# 3_waffling80-NMB_mcu.net
KiCad netlist of a schematic drawn in Altium Designer
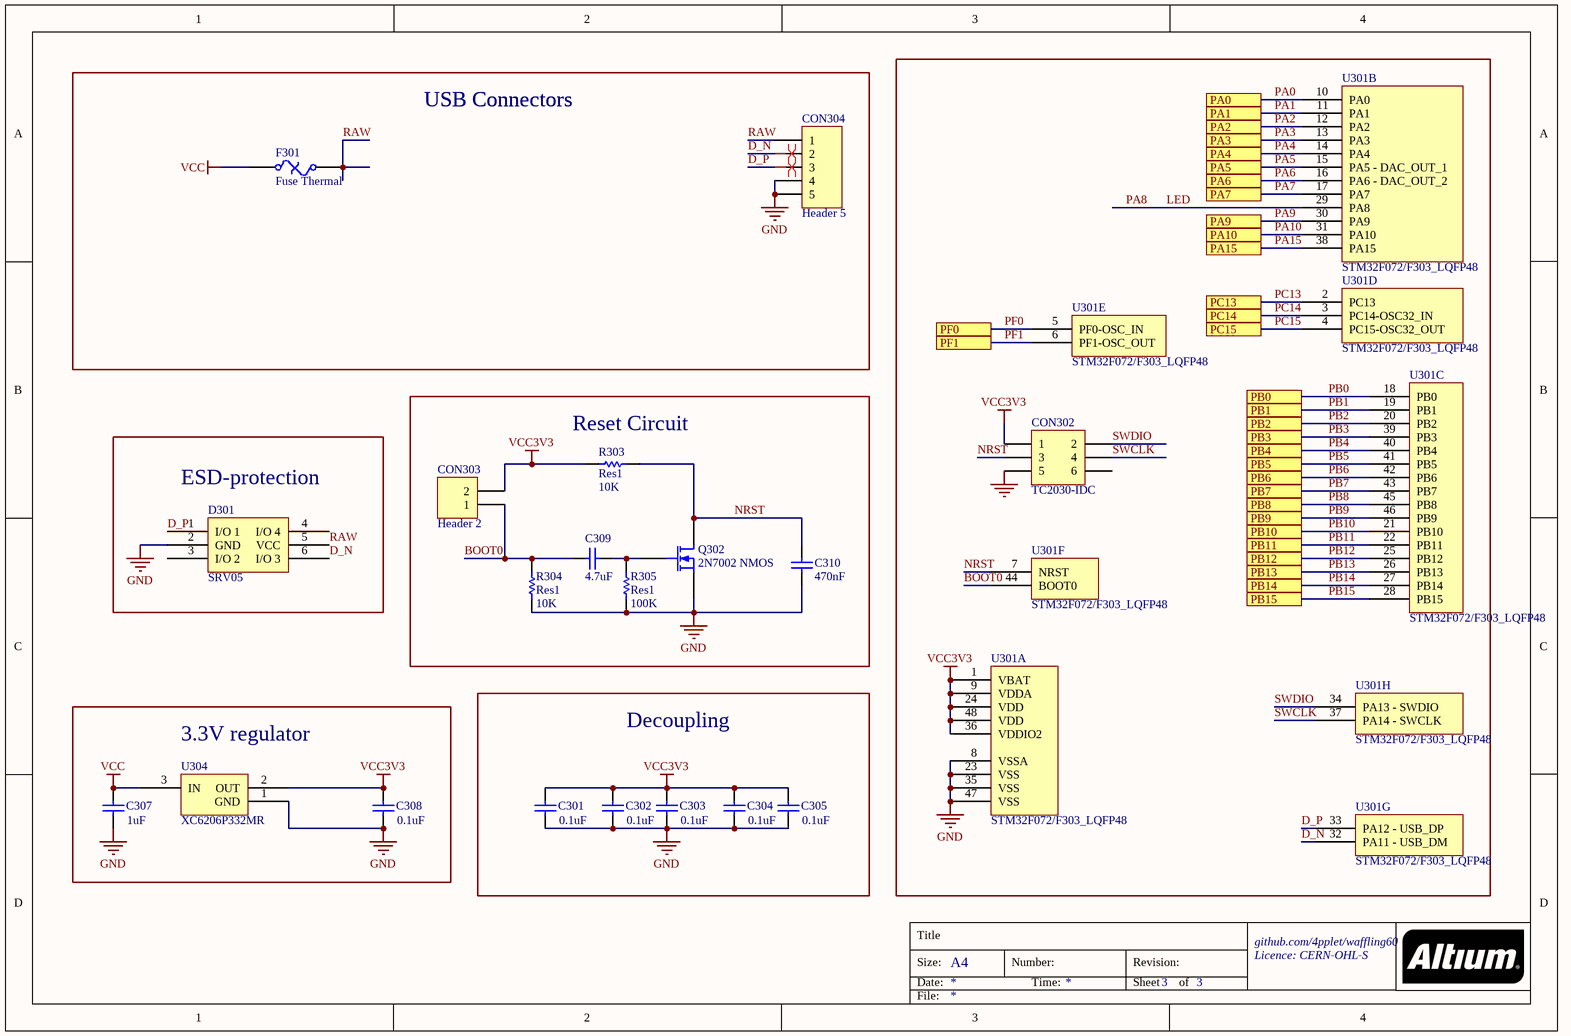
[diagram p0: 3_waffling80-NMB_mcu.SchDoc]

(export (version "E")
  (design (tool "Eeschema 10.0.6"))
  (components
    (comp (ref "C301")
      (value "0.1uF")
      (footprint "C0603[1608]")
      (description "Capacitor")
      (fields (field (name "LCSC PART #") "C14663") (field (name "MRF.PART") "CC0603KRX7R9BB104"))
      (libsource (lib "Miscellaneous Devices") (part "Cap"))
    )
    (comp (ref "C302")
      (value "0.1uF")
      (footprint "C0603[1608]")
      (description "Capacitor")
      (fields (field (name "LCSC PART #") "C14663") (field (name "MRF.PART") "CC0603KRX7R9BB104"))
      (libsource (lib "Miscellaneous Devices") (part "Cap"))
    )
    (comp (ref "C303")
      (value "0.1uF")
      (footprint "C0603[1608]")
      (description "Capacitor")
      (fields (field (name "LCSC PART #") "C14663") (field (name "MRF.PART") "CC0603KRX7R9BB104"))
      (libsource (lib "Miscellaneous Devices") (part "Cap"))
    )
    (comp (ref "C304")
      (value "0.1uF")
      (footprint "C0603[1608]")
      (description "Capacitor")
      (fields (field (name "LCSC PART #") "C14663") (field (name "MRF.PART") "CC0603KRX7R9BB104"))
      (libsource (lib "Miscellaneous Devices") (part "Cap"))
    )
    (comp (ref "C305")
      (value "0.1uF")
      (footprint "C0603[1608]")
      (description "Capacitor")
      (fields (field (name "LCSC PART #") "C14663") (field (name "MRF.PART") "CC0603KRX7R9BB104"))
      (libsource (lib "Miscellaneous Devices") (part "Cap"))
    )
    (comp (ref "C307")
      (value "1uF")
      (footprint "C0603[1608]")
      (description "Capacitor")
      (fields (field (name "LCSC PART #") "C15849") (field (name "MRF.PART") "CL10A105KB8NNNC"))
      (libsource (lib "Miscellaneous Devices") (part "Cap"))
    )
    (comp (ref "C308")
      (value "0.1uF")
      (footprint "C0603[1608]")
      (description "Capacitor")
      (fields (field (name "LCSC PART #") "C14663") (field (name "MRF.PART") "CC0603KRX7R9BB104"))
      (libsource (lib "Miscellaneous Devices") (part "Cap"))
    )
    (comp (ref "C309")
      (value "4.7uF")
      (footprint "C0603[1608]")
      (description "Capacitor")
      (fields (field (name "LCSC PART #") "C19666") (field (name "MRF.PART") "CL10A475KO8NNNC"))
      (libsource (lib "Miscellaneous Devices") (part "Cap"))
    )
    (comp (ref "C310")
      (value "470nF")
      (footprint "C0603[1608]")
      (description "Capacitor")
      (fields (field (name "LCSC PART #") "C1623") (field (name "MRF.PART") "CL10B474KA8NNNC"))
      (libsource (lib "Miscellaneous Devices") (part "Cap"))
    )
    (comp (ref "CON302")
      (value "TC2030-IDC")
      (footprint "TC2030-IDC-NL")
      (description "Header, 3-Pin, Dual row")
      (libsource (lib "Miscellaneous Connectors") (part "Header 3X2"))
    )
    (comp (ref "CON303")
      (value "Header 2")
      (footprint "HDR1X2")
      (description "Header, 2-Pin")
      (libsource (lib "Miscellaneous Connectors") (part "Header 2"))
    )
    (comp (ref "CON304")
      (value "Header 5")
      (footprint "UDB_COMBO_JST_MOLEX")
      (description "JST for USB daughter board")
      (fields (field (name "LCSC PART #") "C160404") (field (name "MRF.PART") "SM04B-SRSS-TB(LF)(SN)"))
      (libsource (lib "Miscellaneous Connectors") (part "Header 5"))
    )
    (comp (ref "D301")
      (value "SRV05")
      (footprint "SOT-23-6")
      (fields (field (name "LCSC PART #") "C85364") (field (name "MRF.PART") "SRV05-4-P-T7"))
      (libsource (lib "Keebs") (part "SRV05"))
    )
    (comp (ref "F301")
      (value "Fuse Thermal")
      (footprint "C1206[3216]")
      (description "Thermal Fuse")
      (fields (field (name "LCSC PART #") "C135338") (field (name "MRF.PART") "ASMD1206-050"))
      (libsource (lib "Miscellaneous Devices") (part "Fuse Thermal"))
    )
    (comp (ref "Q302")
      (value "2N7002 NMOS")
      (footprint "SOT-23-3")
      (description "N-Channel MOSFET")
      (fields (field (name "LCSC PART #") "C8545") (field (name "MRF.PART") "2N7002"))
      (libsource (lib "Miscellaneous Devices") (part "MOSFET-N"))
    )
    (comp (ref "R303")
      (value "Res1")
      (footprint "R0603[1608]")
      (description "Resistor")
      (fields
        (field (name "ALTIUM_VALUE") "10K")
        (field (name "LCSC PART #") "C25804")
        (field (name "MRF.PART") "0603WAF1002T5E")
      )
      (libsource (lib "Miscellaneous Devices") (part "Res1"))
    )
    (comp (ref "R304")
      (value "Res1")
      (footprint "R0603[1608]")
      (description "Resistor")
      (fields
        (field (name "ALTIUM_VALUE") "10K")
        (field (name "LCSC PART #") "C25804")
        (field (name "MRF.PART") "0603WAF1002T5E")
      )
      (libsource (lib "Miscellaneous Devices") (part "Res1"))
    )
    (comp (ref "R305")
      (value "Res1")
      (footprint "R0603[1608]")
      (description "Resistor")
      (fields
        (field (name "ALTIUM_VALUE") "100K")
        (field (name "LCSC PART #") "C25803")
        (field (name "MRF.PART") "0603WAF1003T5E")
      )
      (libsource (lib "Miscellaneous Devices") (part "Res1"))
    )
    (comp (ref "U301")
      (value "STM32F072/F303_LQFP48")
      (footprint "STM32 - COMBO 7X7MM")
      (fields (field (name "LCSC PART #") "C915660") (field (name "MRF.PART") "APM32F072CBT6"))
      (libsource (lib "Keebs") (part "STM32F072/F303_LQFP48"))
    )
    (comp (ref "U304")
      (value "XC6206P332MR")
      (footprint "SOT-23-3")
      (fields (field (name "LCSC PART #") "C5446"))
      (libsource (lib "Keebs") (part "SOT23 LDO"))
    )
  )
  (nets
    (net (code "1") (name "/BOOT0") (class "Default")
      (node (ref "C309") (pin "1") (pinfunction "1_1") (pintype "passive"))
      (node (ref "CON303") (pin "1") (pinfunction "1_1") (pintype "passive"))
      (node (ref "R304") (pin "1") (pinfunction "1_1") (pintype "passive"))
      (node (ref "U301") (pin "44") (pinfunction "BOOT0_44") (pintype "passive"))
    )
    (net (code "2") (name "/D_N") (class "Default")
      (node (ref "CON304") (pin "2") (pinfunction "2_2") (pintype "passive"))
      (node (ref "D301") (pin "6") (pinfunction "I/O_3_6") (pintype "passive"))
      (node (ref "U301") (pin "32") (pinfunction "PA11_-_USB_DM_32") (pintype "passive"))
    )
    (net (code "3") (name "/D_P") (class "Default")
      (node (ref "CON304") (pin "3") (pinfunction "3_3") (pintype "passive"))
      (node (ref "D301") (pin "1") (pinfunction "I/O_1_1") (pintype "passive"))
      (node (ref "U301") (pin "33") (pinfunction "PA12_-_USB_DP_33") (pintype "passive"))
    )
    (net (code "4") (name "/LED") (class "Default")
      (node (ref "U301") (pin "29") (pinfunction "PA8_29") (pintype "passive"))
    )
    (net (code "5") (name "/NRST") (class "Default")
      (node (ref "C310") (pin "1") (pinfunction "1_1") (pintype "passive"))
      (node (ref "CON302") (pin "3") (pinfunction "3_3") (pintype "passive"))
      (node (ref "Q302") (pin "3") (pinfunction "D_3") (pintype "passive"))
      (node (ref "R303") (pin "2") (pinfunction "2_2") (pintype "passive"))
      (node (ref "U301") (pin "7") (pinfunction "NRST_7") (pintype "passive"))
    )
    (net (code "6") (name "/PA0") (class "Default")
      (node (ref "U301") (pin "10") (pinfunction "PA0_10") (pintype "passive"))
    )
    (net (code "7") (name "/PA1") (class "Default")
      (node (ref "U301") (pin "11") (pinfunction "PA1_11") (pintype "passive"))
    )
    (net (code "8") (name "/PA2") (class "Default")
      (node (ref "U301") (pin "12") (pinfunction "PA2_12") (pintype "passive"))
    )
    (net (code "9") (name "/PA3") (class "Default")
      (node (ref "U301") (pin "13") (pinfunction "PA3_13") (pintype "passive"))
    )
    (net (code "10") (name "/PA4") (class "Default")
      (node (ref "U301") (pin "14") (pinfunction "PA4_14") (pintype "passive"))
    )
    (net (code "11") (name "/PA5") (class "Default")
      (node (ref "U301") (pin "15") (pinfunction "PA5_-_DAC_OUT_1_15") (pintype "passive"))
    )
    (net (code "12") (name "/PA6") (class "Default")
      (node (ref "U301") (pin "16") (pinfunction "PA6_-_DAC_OUT_2_16") (pintype "passive"))
    )
    (net (code "13") (name "/PA7") (class "Default")
      (node (ref "U301") (pin "17") (pinfunction "PA7_17") (pintype "passive"))
    )
    (net (code "14") (name "/PA9") (class "Default")
      (node (ref "U301") (pin "30") (pinfunction "PA9_30") (pintype "passive"))
    )
    (net (code "15") (name "/PA10") (class "Default")
      (node (ref "U301") (pin "31") (pinfunction "PA10_31") (pintype "passive"))
    )
    (net (code "16") (name "/PA15") (class "Default")
      (node (ref "U301") (pin "38") (pinfunction "PA15_38") (pintype "passive"))
    )
    (net (code "17") (name "/PB0") (class "Default")
      (node (ref "U301") (pin "18") (pinfunction "PB0_18") (pintype "passive"))
    )
    (net (code "18") (name "/PB1") (class "Default")
      (node (ref "U301") (pin "19") (pinfunction "PB1_19") (pintype "passive"))
    )
    (net (code "19") (name "/PB2") (class "Default")
      (node (ref "U301") (pin "20") (pinfunction "PB2_20") (pintype "passive"))
    )
    (net (code "20") (name "/PB3") (class "Default")
      (node (ref "U301") (pin "39") (pinfunction "PB3_39") (pintype "passive"))
    )
    (net (code "21") (name "/PB4") (class "Default")
      (node (ref "U301") (pin "40") (pinfunction "PB4_40") (pintype "passive"))
    )
    (net (code "22") (name "/PB5") (class "Default")
      (node (ref "U301") (pin "41") (pinfunction "PB5_41") (pintype "passive"))
    )
    (net (code "23") (name "/PB6") (class "Default")
      (node (ref "U301") (pin "42") (pinfunction "PB6_42") (pintype "passive"))
    )
    (net (code "24") (name "/PB7") (class "Default")
      (node (ref "U301") (pin "43") (pinfunction "PB7_43") (pintype "passive"))
    )
    (net (code "25") (name "/PB8") (class "Default")
      (node (ref "U301") (pin "45") (pinfunction "PB8_45") (pintype "passive"))
    )
    (net (code "26") (name "/PB9") (class "Default")
      (node (ref "U301") (pin "46") (pinfunction "PB9_46") (pintype "passive"))
    )
    (net (code "27") (name "/PB10") (class "Default")
      (node (ref "U301") (pin "21") (pinfunction "PB10_21") (pintype "passive"))
    )
    (net (code "28") (name "/PB11") (class "Default")
      (node (ref "U301") (pin "22") (pinfunction "PB11_22") (pintype "passive"))
    )
    (net (code "29") (name "/PB12") (class "Default")
      (node (ref "U301") (pin "25") (pinfunction "PB12_25") (pintype "passive"))
    )
    (net (code "30") (name "/PB13") (class "Default")
      (node (ref "U301") (pin "26") (pinfunction "PB13_26") (pintype "passive"))
    )
    (net (code "31") (name "/PB14") (class "Default")
      (node (ref "U301") (pin "27") (pinfunction "PB14_27") (pintype "passive"))
    )
    (net (code "32") (name "/PB15") (class "Default")
      (node (ref "U301") (pin "28") (pinfunction "PB15_28") (pintype "passive"))
    )
    (net (code "33") (name "/PC13") (class "Default")
      (node (ref "U301") (pin "2") (pinfunction "PC13_2") (pintype "passive"))
    )
    (net (code "34") (name "/PC14") (class "Default")
      (node (ref "U301") (pin "3") (pinfunction "PC14-OSC32_IN_3") (pintype "passive"))
    )
    (net (code "35") (name "/PC15") (class "Default")
      (node (ref "U301") (pin "4") (pinfunction "PC15-OSC32_OUT_4") (pintype "passive"))
    )
    (net (code "36") (name "/PF0") (class "Default")
      (node (ref "U301") (pin "5") (pinfunction "PF0-OSC_IN_5") (pintype "passive"))
    )
    (net (code "37") (name "/PF1") (class "Default")
      (node (ref "U301") (pin "6") (pinfunction "PF1-OSC_OUT_6") (pintype "passive"))
    )
    (net (code "38") (name "/RAW") (class "Default")
      (node (ref "CON304") (pin "1") (pinfunction "1_1") (pintype "passive"))
      (node (ref "D301") (pin "5") (pinfunction "VCC_5") (pintype "passive"))
      (node (ref "F301") (pin "2") (pinfunction "2_2") (pintype "passive"))
    )
    (net (code "39") (name "/SWCLK") (class "Default")
      (node (ref "CON302") (pin "4") (pinfunction "4_4") (pintype "passive"))
      (node (ref "U301") (pin "37") (pinfunction "PA14_-_SWCLK_37") (pintype "passive"))
    )
    (net (code "40") (name "/SWDIO") (class "Default")
      (node (ref "CON302") (pin "2") (pinfunction "2_2") (pintype "passive"))
      (node (ref "U301") (pin "34") (pinfunction "PA13_-_SWDIO_34") (pintype "passive"))
    )
    (net (code "41") (name "GND") (class "Default")
      (node (ref "C301") (pin "1") (pinfunction "1_1") (pintype "passive"))
      (node (ref "C302") (pin "1") (pinfunction "1_1") (pintype "passive"))
      (node (ref "C303") (pin "1") (pinfunction "1_1") (pintype "passive"))
      (node (ref "C304") (pin "1") (pinfunction "1_1") (pintype "passive"))
      (node (ref "C305") (pin "1") (pinfunction "1_1") (pintype "passive"))
      (node (ref "C307") (pin "1") (pinfunction "1_1") (pintype "passive"))
      (node (ref "C308") (pin "1") (pinfunction "1_1") (pintype "passive"))
      (node (ref "C310") (pin "2") (pinfunction "2_2") (pintype "passive"))
      (node (ref "CON302") (pin "5") (pinfunction "5_5") (pintype "passive"))
      (node (ref "CON304") (pin "4") (pinfunction "4_4") (pintype "passive"))
      (node (ref "CON304") (pin "5") (pinfunction "5_5") (pintype "passive"))
      (node (ref "D301") (pin "2") (pinfunction "GND_2") (pintype "passive"))
      (node (ref "Q302") (pin "2") (pinfunction "S_2") (pintype "passive"))
      (node (ref "R304") (pin "2") (pinfunction "2_2") (pintype "passive"))
      (node (ref "R305") (pin "2") (pinfunction "2_2") (pintype "passive"))
      (node (ref "U301") (pin "23") (pinfunction "VSS_23") (pintype "passive"))
      (node (ref "U301") (pin "35") (pinfunction "VSS_35") (pintype "passive"))
      (node (ref "U301") (pin "47") (pinfunction "VSS_47") (pintype "passive"))
      (node (ref "U301") (pin "8") (pinfunction "VSSA_8") (pintype "passive"))
      (node (ref "U304") (pin "1") (pinfunction "GND_1") (pintype "passive"))
    )
    (net (code "42") (name "Net-(Q302-G)") (class "Default")
      (node (ref "C309") (pin "2") (pinfunction "2_2") (pintype "passive"))
      (node (ref "Q302") (pin "1") (pinfunction "G_1") (pintype "passive"))
      (node (ref "R305") (pin "1") (pinfunction "1_1") (pintype "passive"))
    )
    (net (code "43") (name "VCC") (class "Default")
      (node (ref "C307") (pin "2") (pinfunction "2_2") (pintype "passive"))
      (node (ref "F301") (pin "1") (pinfunction "1_1") (pintype "passive"))
      (node (ref "U304") (pin "3") (pinfunction "IN_3") (pintype "passive"))
    )
    (net (code "44") (name "VCC3V3") (class "Default")
      (node (ref "C301") (pin "2") (pinfunction "2_2") (pintype "passive"))
      (node (ref "C302") (pin "2") (pinfunction "2_2") (pintype "passive"))
      (node (ref "C303") (pin "2") (pinfunction "2_2") (pintype "passive"))
      (node (ref "C304") (pin "2") (pinfunction "2_2") (pintype "passive"))
      (node (ref "C305") (pin "2") (pinfunction "2_2") (pintype "passive"))
      (node (ref "C308") (pin "2") (pinfunction "2_2") (pintype "passive"))
      (node (ref "CON302") (pin "1") (pinfunction "1_1") (pintype "passive"))
      (node (ref "CON303") (pin "2") (pinfunction "2_2") (pintype "passive"))
      (node (ref "R303") (pin "1") (pinfunction "1_1") (pintype "passive"))
      (node (ref "U301") (pin "1") (pinfunction "VBAT_1") (pintype "passive"))
      (node (ref "U301") (pin "24") (pinfunction "VDD_24") (pintype "passive"))
      (node (ref "U301") (pin "36") (pinfunction "VDDIO2_36") (pintype "passive"))
      (node (ref "U301") (pin "48") (pinfunction "VDD_48") (pintype "passive"))
      (node (ref "U301") (pin "9") (pinfunction "VDDA_9") (pintype "passive"))
      (node (ref "U304") (pin "2") (pinfunction "OUT_2") (pintype "passive"))
    )
    (net (code "45") (name "unconnected-(CON302-Pad6)") (class "Default")
      (node (ref "CON302") (pin "6") (pinfunction "6_6") (pintype "passive"))
    )
    (net (code "46") (name "unconnected-(D301-I{slash}O_2-Pad3)") (class "Default")
      (node (ref "D301") (pin "3") (pinfunction "I/O_2_3") (pintype "passive"))
    )
    (net (code "47") (name "unconnected-(D301-I{slash}O_4-Pad4)") (class "Default")
      (node (ref "D301") (pin "4") (pinfunction "I/O_4_4") (pintype "passive"))
    )
  )
)
